# 00A-010.net
KiCad netlist of a schematic drawn in EAGLE
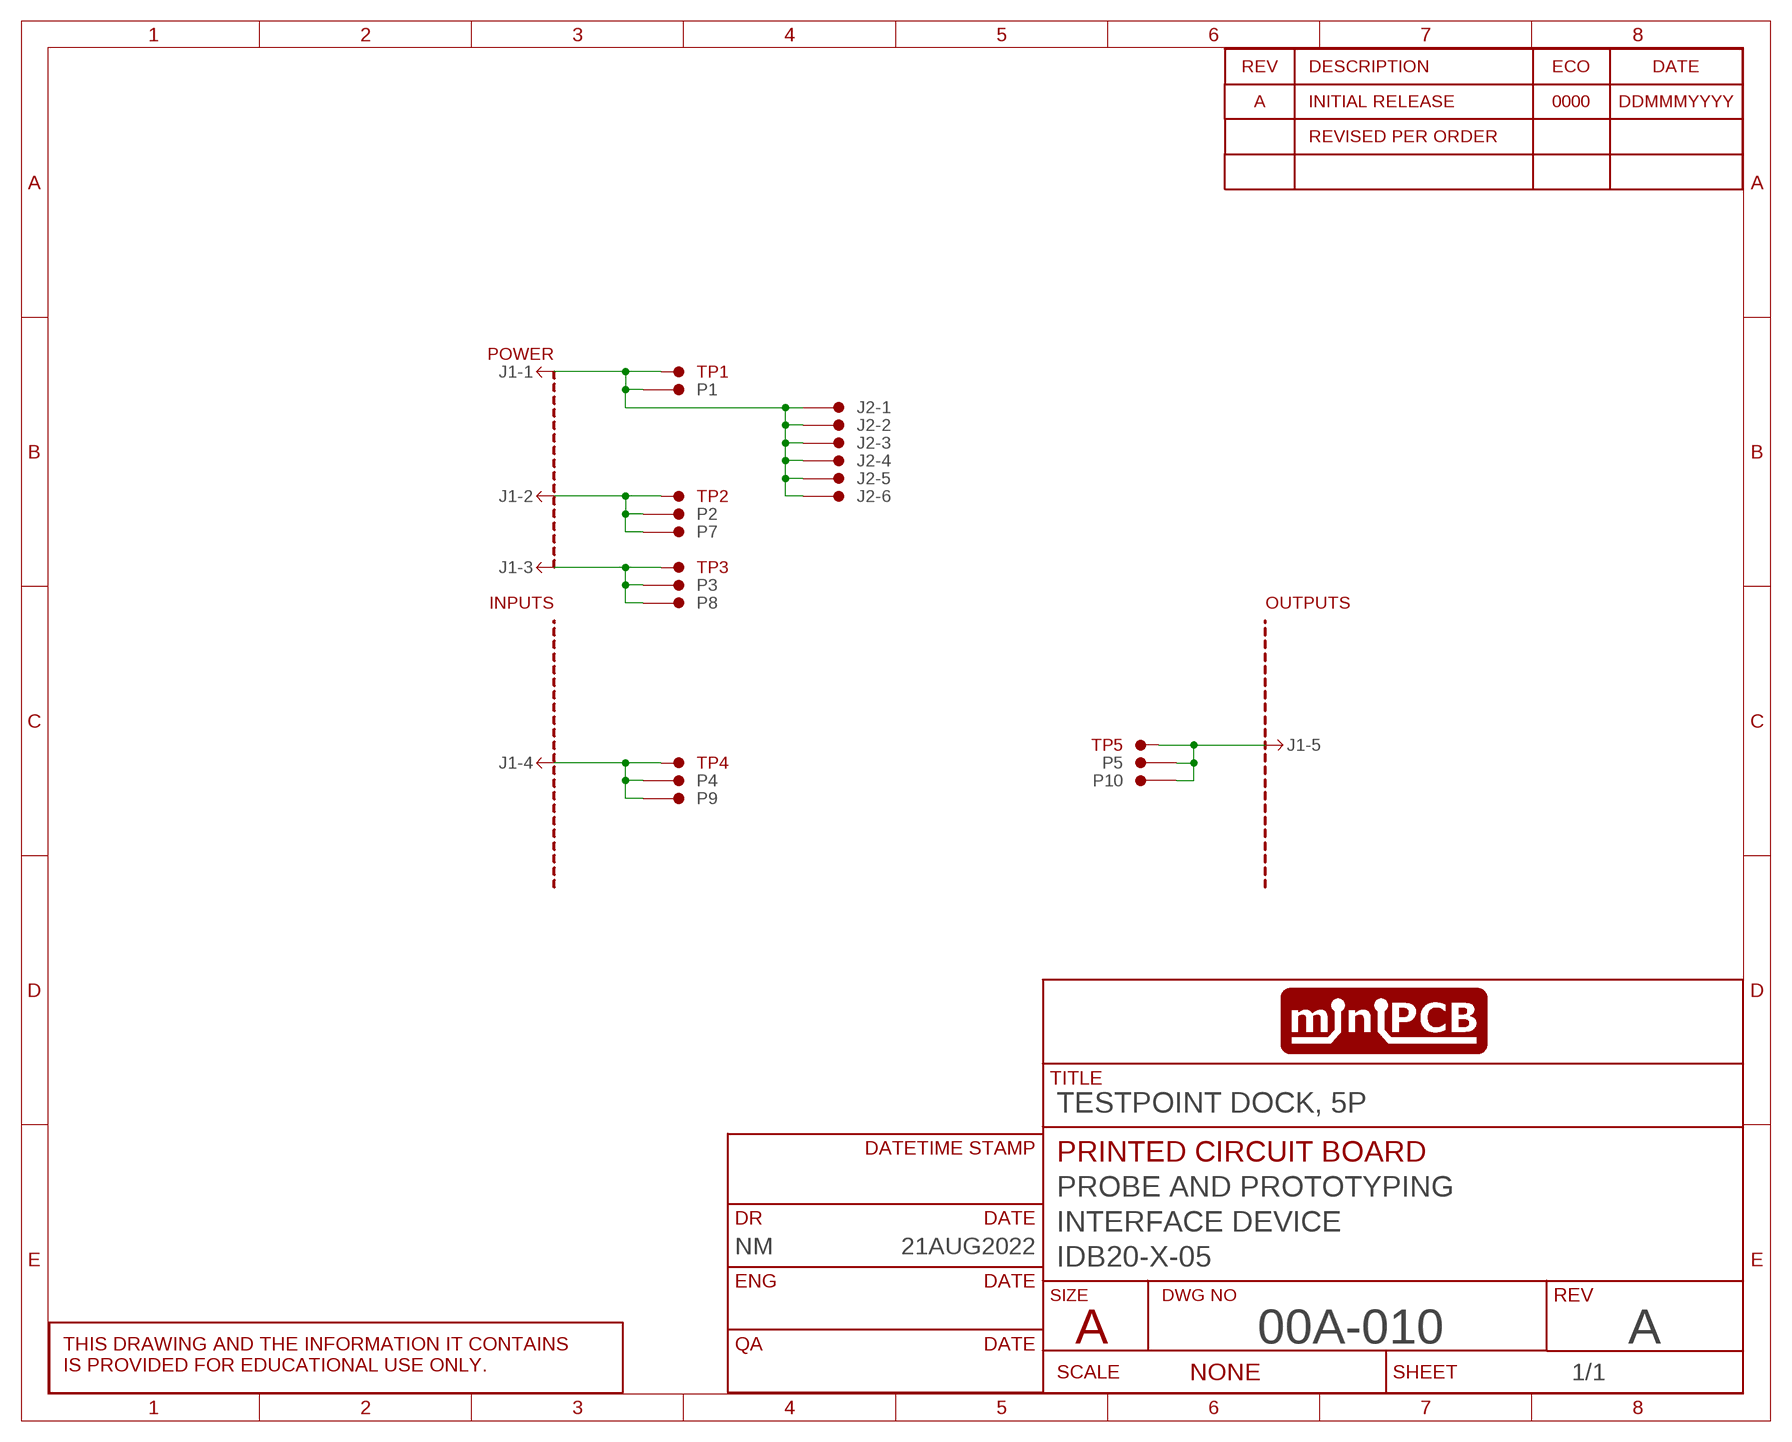
[diagram p0: schematic, sheet 1]

(export (version "E")
  (design (tool "Eeschema 10.0.6"))
  (components
    (comp (ref "J1")
      (value "MINIPCB_IDB20-X-05")
      (footprint "eagle-import:MINIPCB_IDB20-X-05")
      (fields (field (name "PART_NUMBER_REV") "00A-010-B"))
      (libsource (lib "eagle-import") (part "MINIPCB_IDB20-X-05"))
    )
    (comp (ref "J2")
      (value "PINS_6NOTEXT")
      (footprint "eagle-import:PINS_6_NOTEXT")
      (libsource (lib "eagle-import") (part "PINS_6NOTEXT"))
    )
    (comp (ref "P1")
      (value "PINS_124AWG-K")
      (footprint "eagle-import:PINS_1_1MM_K")
      (libsource (lib "eagle-import") (part "PINS_124AWG-K"))
    )
    (comp (ref "P2")
      (value "PINS_12P")
      (footprint "eagle-import:PINS_2_NOTEXT")
      (libsource (lib "eagle-import") (part "PINS_12P"))
    )
    (comp (ref "P3")
      (value "PINS_12P")
      (footprint "eagle-import:PINS_2_NOTEXT")
      (libsource (lib "eagle-import") (part "PINS_12P"))
    )
    (comp (ref "P4")
      (value "PINS_12P")
      (footprint "eagle-import:PINS_2_NOTEXT")
      (libsource (lib "eagle-import") (part "PINS_12P"))
    )
    (comp (ref "P5")
      (value "PINS_12P")
      (footprint "eagle-import:PINS_2_NOTEXT")
      (libsource (lib "eagle-import") (part "PINS_12P"))
    )
    (comp (ref "P7")
      (value "PINS_124AWG-K")
      (footprint "eagle-import:PINS_1_1MM_K")
      (libsource (lib "eagle-import") (part "PINS_124AWG-K"))
    )
    (comp (ref "P8")
      (value "PINS_124AWG-K")
      (footprint "eagle-import:PINS_1_1MM_K")
      (libsource (lib "eagle-import") (part "PINS_124AWG-K"))
    )
    (comp (ref "P9")
      (value "PINS_124AWG-K")
      (footprint "eagle-import:PINS_1_1MM_K")
      (libsource (lib "eagle-import") (part "PINS_124AWG-K"))
    )
    (comp (ref "P10")
      (value "PINS_124AWG-K")
      (footprint "eagle-import:PINS_1_1MM_K")
      (libsource (lib "eagle-import") (part "PINS_124AWG-K"))
    )
    (comp (ref "TP1")
      (value "TESTPOINTKE5000")
      (footprint "eagle-import:PINS_1_TESTPOINT_KE5000")
      (libsource (lib "eagle-import") (part "TESTPOINTKE5000"))
    )
    (comp (ref "TP2")
      (value "TESTPOINTKE5000")
      (footprint "eagle-import:PINS_1_TESTPOINT_KE5000")
      (libsource (lib "eagle-import") (part "TESTPOINTKE5000"))
    )
    (comp (ref "TP3")
      (value "TESTPOINTKE5000")
      (footprint "eagle-import:PINS_1_TESTPOINT_KE5000")
      (libsource (lib "eagle-import") (part "TESTPOINTKE5000"))
    )
    (comp (ref "TP4")
      (value "TESTPOINTKE5000")
      (footprint "eagle-import:PINS_1_TESTPOINT_KE5000")
      (libsource (lib "eagle-import") (part "TESTPOINTKE5000"))
    )
    (comp (ref "TP5")
      (value "TESTPOINTKE5000")
      (footprint "eagle-import:PINS_1_TESTPOINT_KE5000")
      (libsource (lib "eagle-import") (part "TESTPOINTKE5000"))
    )
  )
  (nets
    (net (code "1") (name "Net-(J1B-1)") (class "Default")
      (node (ref "J1") (pin "2") (pinfunction "1_2") (pintype "bidirectional"))
      (node (ref "P2") (pin "1") (pinfunction "1_1") (pintype "bidirectional"))
      (node (ref "P2") (pin "2") (pinfunction "1_2") (pintype "bidirectional"))
      (node (ref "P7") (pin "1") (pinfunction "1_1") (pintype "bidirectional"))
      (node (ref "P7") (pin "2") (pinfunction "1_2") (pintype "bidirectional"))
      (node (ref "TP2") (pin "1") (pinfunction "1_1") (pintype "bidirectional"))
    )
    (net (code "2") (name "Net-(J1C-1)") (class "Default")
      (node (ref "J1") (pin "3") (pinfunction "1_3") (pintype "bidirectional"))
      (node (ref "P3") (pin "1") (pinfunction "1_1") (pintype "bidirectional"))
      (node (ref "P3") (pin "2") (pinfunction "1_2") (pintype "bidirectional"))
      (node (ref "P8") (pin "1") (pinfunction "1_1") (pintype "bidirectional"))
      (node (ref "P8") (pin "2") (pinfunction "1_2") (pintype "bidirectional"))
      (node (ref "TP3") (pin "1") (pinfunction "1_1") (pintype "bidirectional"))
    )
    (net (code "3") (name "Net-(J1D-1)") (class "Default")
      (node (ref "J1") (pin "4") (pinfunction "1_4") (pintype "bidirectional"))
      (node (ref "P4") (pin "1") (pinfunction "1_1") (pintype "bidirectional"))
      (node (ref "P4") (pin "2") (pinfunction "1_2") (pintype "bidirectional"))
      (node (ref "P9") (pin "1") (pinfunction "1_1") (pintype "bidirectional"))
      (node (ref "P9") (pin "2") (pinfunction "1_2") (pintype "bidirectional"))
      (node (ref "TP4") (pin "1") (pinfunction "1_1") (pintype "bidirectional"))
    )
    (net (code "4") (name "Net-(J1E-1)") (class "Default")
      (node (ref "J1") (pin "5") (pinfunction "1_5") (pintype "bidirectional"))
      (node (ref "P10") (pin "1") (pinfunction "1_1") (pintype "bidirectional"))
      (node (ref "P10") (pin "2") (pinfunction "1_2") (pintype "bidirectional"))
      (node (ref "P5") (pin "1") (pinfunction "1_1") (pintype "bidirectional"))
      (node (ref "P5") (pin "2") (pinfunction "1_2") (pintype "bidirectional"))
      (node (ref "TP5") (pin "1") (pinfunction "1_1") (pintype "bidirectional"))
    )
    (net (code "5") (name "Net-(J2B-1)") (class "Default")
      (node (ref "J1") (pin "1") (pinfunction "1_1") (pintype "bidirectional"))
      (node (ref "J2") (pin "1") (pinfunction "1_1") (pintype "bidirectional"))
      (node (ref "J2") (pin "2") (pinfunction "1_2") (pintype "bidirectional"))
      (node (ref "J2") (pin "3") (pinfunction "1_3") (pintype "bidirectional"))
      (node (ref "J2") (pin "4") (pinfunction "1_4") (pintype "bidirectional"))
      (node (ref "J2") (pin "5") (pinfunction "1_5") (pintype "bidirectional"))
      (node (ref "J2") (pin "6") (pinfunction "1_6") (pintype "bidirectional"))
      (node (ref "P1") (pin "1") (pinfunction "1_1") (pintype "bidirectional"))
      (node (ref "P1") (pin "2") (pinfunction "1_2") (pintype "bidirectional"))
      (node (ref "TP1") (pin "1") (pinfunction "1_1") (pintype "bidirectional"))
    )
  )
)
